# 12_Supply.net
KiCad netlist of a schematic drawn in Altium Designer
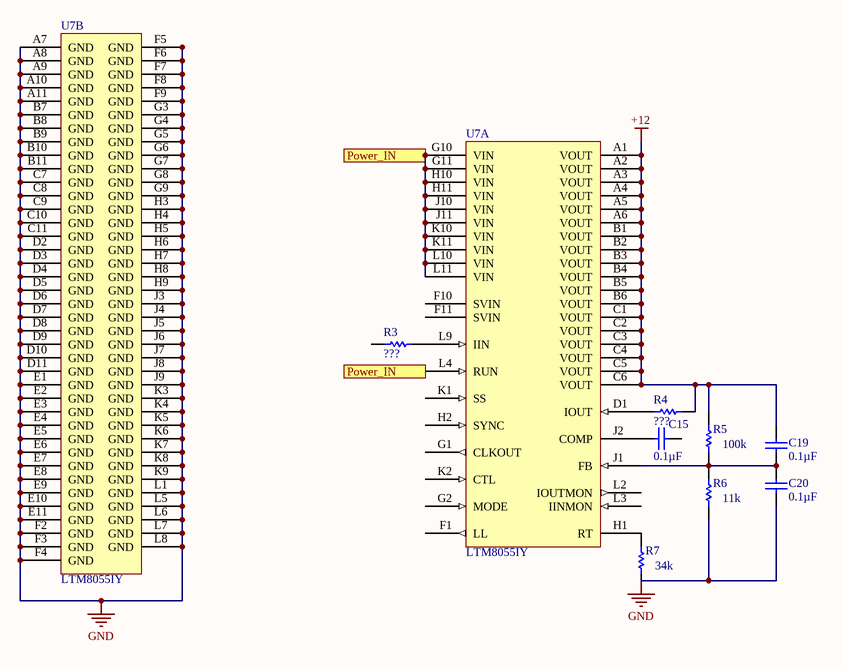
[diagram p0: 12_Supply.SchDoc]

(export (version "E")
  (design (tool "Eeschema 10.0.6"))
  (components
    (comp (ref "C15")
      (value "CAP CER 0.1UF 16V X7R 0805")
      (footprint "CAPC0805(2012)145_N")
      (fields
        (field (name "TOLERANCE") "±10%")
        (field (name "MANUFACTURER") "Murata Electronics North America")
        (field (name "MANUFACTURER PART NUMBER") "GRM219R71C104KA01D")
        (field (name "CAPACITANCE") "0.1µF")
      )
      (libsource (lib "Altium Content Vault") (part "CMP-1036-04795-1"))
    )
    (comp (ref "C19")
      (value "CAP CER 0.1UF 16V X7R 0805")
      (footprint "CAPC0805(2012)145_N")
      (fields
        (field (name "TOLERANCE") "±10%")
        (field (name "MANUFACTURER") "Murata Electronics North America")
        (field (name "MANUFACTURER PART NUMBER") "GRM219R71C104KA01D")
        (field (name "CAPACITANCE") "0.1µF")
      )
      (libsource (lib "Altium Content Vault") (part "CMP-1036-04795-1"))
    )
    (comp (ref "C20")
      (value "CAP CER 0.1UF 16V X7R 0805")
      (footprint "CAPC0805(2012)145_N")
      (fields
        (field (name "TOLERANCE") "±10%")
        (field (name "MANUFACTURER") "Murata Electronics North America")
        (field (name "MANUFACTURER PART NUMBER") "GRM219R71C104KA01D")
        (field (name "CAPACITANCE") "0.1µF")
      )
      (libsource (lib "Altium Content Vault") (part "CMP-1036-04795-1"))
    )
    (comp (ref "R3")
      (value "???")
      (footprint "RESC0402(1005)_L")
      (fields (field (name "TOLERANCE") "±1%"))
      (libsource (lib "Altium Content Vault") (part "CMP-1011-00927-1"))
    )
    (comp (ref "R4")
      (value "???")
      (footprint "RESC0402(1005)_L")
      (fields (field (name "TOLERANCE") "±1%"))
      (libsource (lib "Altium Content Vault") (part "CMP-1011-00927-1"))
    )
    (comp (ref "R5")
      (value "100k")
      (footprint "RESC0402(1005)_L")
      (fields (field (name "TOLERANCE") "±1%"))
      (libsource (lib "Altium Content Vault") (part "CMP-1011-00927-1"))
    )
    (comp (ref "R6")
      (value "11k")
      (footprint "RESC0402(1005)_L")
      (fields (field (name "TOLERANCE") "±1%"))
      (libsource (lib "Altium Content Vault") (part "CMP-1011-00927-1"))
    )
    (comp (ref "R7")
      (value "34k")
      (footprint "RESC0402(1005)_L")
      (fields (field (name "TOLERANCE") "±1%"))
      (libsource (lib "Altium Content Vault") (part "CMP-1011-00927-1"))
    )
    (comp (ref "U7")
      (value "LTM8055IY")
      (footprint "LT-BGA-121-15000X15000X4920")
      (description "Buck-Boost uModule Regulator, 8.5 A, 5 to 36 V, -40 to 125 degC, 121-Ball BGA, RoHS, Tray")
      (fields (field (name "MANUFACTURER") "LinearTechnology"))
      (libsource (lib "Altium Content Vault") (part "LT-LTM8055-BGA-121"))
    )
  )
  (nets
    (net (code "1") (name "+12") (class "Default")
      (node (ref "C19") (pin "2") (pinfunction "2_2") (pintype "passive"))
      (node (ref "R4") (pin "1") (pinfunction "1_1") (pintype "passive"))
      (node (ref "R5") (pin "2") (pinfunction "2_2") (pintype "passive"))
      (node (ref "U7") (pin "A1") (pinfunction "VOUT_A1") (pintype "power_in"))
      (node (ref "U7") (pin "A2") (pinfunction "VOUT_A2") (pintype "power_in"))
      (node (ref "U7") (pin "A3") (pinfunction "VOUT_A3") (pintype "power_in"))
      (node (ref "U7") (pin "A4") (pinfunction "VOUT_A4") (pintype "power_in"))
      (node (ref "U7") (pin "A5") (pinfunction "VOUT_A5") (pintype "power_in"))
      (node (ref "U7") (pin "A6") (pinfunction "VOUT_A6") (pintype "power_in"))
      (node (ref "U7") (pin "B1") (pinfunction "VOUT_B1") (pintype "power_in"))
      (node (ref "U7") (pin "B2") (pinfunction "VOUT_B2") (pintype "power_in"))
      (node (ref "U7") (pin "B3") (pinfunction "VOUT_B3") (pintype "power_in"))
      (node (ref "U7") (pin "B4") (pinfunction "VOUT_B4") (pintype "power_in"))
      (node (ref "U7") (pin "B5") (pinfunction "VOUT_B5") (pintype "power_in"))
      (node (ref "U7") (pin "B6") (pinfunction "VOUT_B6") (pintype "power_in"))
      (node (ref "U7") (pin "C1") (pinfunction "VOUT_C1") (pintype "power_in"))
      (node (ref "U7") (pin "C2") (pinfunction "VOUT_C2") (pintype "power_in"))
      (node (ref "U7") (pin "C3") (pinfunction "VOUT_C3") (pintype "power_in"))
      (node (ref "U7") (pin "C4") (pinfunction "VOUT_C4") (pintype "power_in"))
      (node (ref "U7") (pin "C5") (pinfunction "VOUT_C5") (pintype "power_in"))
      (node (ref "U7") (pin "C6") (pinfunction "VOUT_C6") (pintype "power_in"))
    )
    (net (code "2") (name "/Power_IN") (class "Default")
      (node (ref "U7") (pin "G10") (pinfunction "VIN_G10") (pintype "power_in"))
      (node (ref "U7") (pin "G11") (pinfunction "VIN_G11") (pintype "power_in"))
      (node (ref "U7") (pin "H10") (pinfunction "VIN_H10") (pintype "power_in"))
      (node (ref "U7") (pin "H11") (pinfunction "VIN_H11") (pintype "power_in"))
      (node (ref "U7") (pin "J10") (pinfunction "VIN_J10") (pintype "power_in"))
      (node (ref "U7") (pin "J11") (pinfunction "VIN_J11") (pintype "power_in"))
      (node (ref "U7") (pin "K10") (pinfunction "VIN_K10") (pintype "power_in"))
      (node (ref "U7") (pin "K11") (pinfunction "VIN_K11") (pintype "power_in"))
      (node (ref "U7") (pin "L10") (pinfunction "VIN_L10") (pintype "power_in"))
      (node (ref "U7") (pin "L11") (pinfunction "VIN_L11") (pintype "power_in"))
      (node (ref "U7") (pin "L4") (pinfunction "RUN_L4") (pintype "input"))
    )
    (net (code "3") (name "GND") (class "Default")
      (node (ref "C20") (pin "1") (pinfunction "1_1") (pintype "passive"))
      (node (ref "R6") (pin "1") (pinfunction "1_1") (pintype "passive"))
      (node (ref "U7") (pin "A10") (pinfunction "GND_A10") (pintype "power_in"))
      (node (ref "U7") (pin "A11") (pinfunction "GND_A11") (pintype "power_in"))
      (node (ref "U7") (pin "A7") (pinfunction "GND_A7") (pintype "power_in"))
      (node (ref "U7") (pin "A8") (pinfunction "GND_A8") (pintype "power_in"))
      (node (ref "U7") (pin "A9") (pinfunction "GND_A9") (pintype "power_in"))
      (node (ref "U7") (pin "B10") (pinfunction "GND_B10") (pintype "power_in"))
      (node (ref "U7") (pin "B11") (pinfunction "GND_B11") (pintype "power_in"))
      (node (ref "U7") (pin "B7") (pinfunction "GND_B7") (pintype "power_in"))
      (node (ref "U7") (pin "B8") (pinfunction "GND_B8") (pintype "power_in"))
      (node (ref "U7") (pin "B9") (pinfunction "GND_B9") (pintype "power_in"))
      (node (ref "U7") (pin "C10") (pinfunction "GND_C10") (pintype "power_in"))
      (node (ref "U7") (pin "C11") (pinfunction "GND_C11") (pintype "power_in"))
      (node (ref "U7") (pin "C7") (pinfunction "GND_C7") (pintype "power_in"))
      (node (ref "U7") (pin "C8") (pinfunction "GND_C8") (pintype "power_in"))
      (node (ref "U7") (pin "C9") (pinfunction "GND_C9") (pintype "power_in"))
      (node (ref "U7") (pin "D10") (pinfunction "GND_D10") (pintype "power_in"))
      (node (ref "U7") (pin "D11") (pinfunction "GND_D11") (pintype "power_in"))
      (node (ref "U7") (pin "D2") (pinfunction "GND_D2") (pintype "power_in"))
      (node (ref "U7") (pin "D3") (pinfunction "GND_D3") (pintype "power_in"))
      (node (ref "U7") (pin "D4") (pinfunction "GND_D4") (pintype "power_in"))
      (node (ref "U7") (pin "D5") (pinfunction "GND_D5") (pintype "power_in"))
      (node (ref "U7") (pin "D6") (pinfunction "GND_D6") (pintype "power_in"))
      (node (ref "U7") (pin "D7") (pinfunction "GND_D7") (pintype "power_in"))
      (node (ref "U7") (pin "D8") (pinfunction "GND_D8") (pintype "power_in"))
      (node (ref "U7") (pin "D9") (pinfunction "GND_D9") (pintype "power_in"))
      (node (ref "U7") (pin "E1") (pinfunction "GND_E1") (pintype "power_in"))
      (node (ref "U7") (pin "E10") (pinfunction "GND_E10") (pintype "power_in"))
      (node (ref "U7") (pin "E11") (pinfunction "GND_E11") (pintype "power_in"))
      (node (ref "U7") (pin "E2") (pinfunction "GND_E2") (pintype "power_in"))
      (node (ref "U7") (pin "E3") (pinfunction "GND_E3") (pintype "power_in"))
      (node (ref "U7") (pin "E4") (pinfunction "GND_E4") (pintype "power_in"))
      (node (ref "U7") (pin "E5") (pinfunction "GND_E5") (pintype "power_in"))
      (node (ref "U7") (pin "E6") (pinfunction "GND_E6") (pintype "power_in"))
      (node (ref "U7") (pin "E7") (pinfunction "GND_E7") (pintype "power_in"))
      (node (ref "U7") (pin "E8") (pinfunction "GND_E8") (pintype "power_in"))
      (node (ref "U7") (pin "E9") (pinfunction "GND_E9") (pintype "power_in"))
      (node (ref "U7") (pin "F2") (pinfunction "GND_F2") (pintype "power_in"))
      (node (ref "U7") (pin "F3") (pinfunction "GND_F3") (pintype "power_in"))
      (node (ref "U7") (pin "F4") (pinfunction "GND_F4") (pintype "power_in"))
      (node (ref "U7") (pin "F5") (pinfunction "GND_F5") (pintype "power_in"))
      (node (ref "U7") (pin "F6") (pinfunction "GND_F6") (pintype "power_in"))
      (node (ref "U7") (pin "F7") (pinfunction "GND_F7") (pintype "power_in"))
      (node (ref "U7") (pin "F8") (pinfunction "GND_F8") (pintype "power_in"))
      (node (ref "U7") (pin "F9") (pinfunction "GND_F9") (pintype "power_in"))
      (node (ref "U7") (pin "G3") (pinfunction "GND_G3") (pintype "power_in"))
      (node (ref "U7") (pin "G4") (pinfunction "GND_G4") (pintype "power_in"))
      (node (ref "U7") (pin "G5") (pinfunction "GND_G5") (pintype "power_in"))
      (node (ref "U7") (pin "G6") (pinfunction "GND_G6") (pintype "power_in"))
      (node (ref "U7") (pin "G7") (pinfunction "GND_G7") (pintype "power_in"))
      (node (ref "U7") (pin "G8") (pinfunction "GND_G8") (pintype "power_in"))
      (node (ref "U7") (pin "G9") (pinfunction "GND_G9") (pintype "power_in"))
      (node (ref "U7") (pin "H3") (pinfunction "GND_H3") (pintype "power_in"))
      (node (ref "U7") (pin "H4") (pinfunction "GND_H4") (pintype "power_in"))
      (node (ref "U7") (pin "H5") (pinfunction "GND_H5") (pintype "power_in"))
      (node (ref "U7") (pin "H6") (pinfunction "GND_H6") (pintype "power_in"))
      (node (ref "U7") (pin "H7") (pinfunction "GND_H7") (pintype "power_in"))
      (node (ref "U7") (pin "H8") (pinfunction "GND_H8") (pintype "power_in"))
      (node (ref "U7") (pin "H9") (pinfunction "GND_H9") (pintype "power_in"))
      (node (ref "U7") (pin "J3") (pinfunction "GND_J3") (pintype "power_in"))
      (node (ref "U7") (pin "J4") (pinfunction "GND_J4") (pintype "power_in"))
      (node (ref "U7") (pin "J5") (pinfunction "GND_J5") (pintype "power_in"))
      (node (ref "U7") (pin "J6") (pinfunction "GND_J6") (pintype "power_in"))
      (node (ref "U7") (pin "J7") (pinfunction "GND_J7") (pintype "power_in"))
      (node (ref "U7") (pin "J8") (pinfunction "GND_J8") (pintype "power_in"))
      (node (ref "U7") (pin "J9") (pinfunction "GND_J9") (pintype "power_in"))
      (node (ref "U7") (pin "K3") (pinfunction "GND_K3") (pintype "power_in"))
      (node (ref "U7") (pin "K4") (pinfunction "GND_K4") (pintype "power_in"))
      (node (ref "U7") (pin "K5") (pinfunction "GND_K5") (pintype "power_in"))
      (node (ref "U7") (pin "K6") (pinfunction "GND_K6") (pintype "power_in"))
      (node (ref "U7") (pin "K7") (pinfunction "GND_K7") (pintype "power_in"))
      (node (ref "U7") (pin "K8") (pinfunction "GND_K8") (pintype "power_in"))
      (node (ref "U7") (pin "K9") (pinfunction "GND_K9") (pintype "power_in"))
      (node (ref "U7") (pin "L1") (pinfunction "GND_L1") (pintype "power_in"))
      (node (ref "U7") (pin "L5") (pinfunction "GND_L5") (pintype "power_in"))
      (node (ref "U7") (pin "L6") (pinfunction "GND_L6") (pintype "power_in"))
      (node (ref "U7") (pin "L7") (pinfunction "GND_L7") (pintype "power_in"))
      (node (ref "U7") (pin "L8") (pinfunction "GND_L8") (pintype "power_in"))
    )
    (net (code "4") (name "Net-(U7A-COMP)") (class "Default")
      (node (ref "C15") (pin "1") (pinfunction "1_1") (pintype "passive"))
      (node (ref "U7") (pin "J2") (pinfunction "COMP_J2") (pintype "passive"))
    )
    (net (code "5") (name "Net-(U7A-FB)") (class "Default")
      (node (ref "C19") (pin "1") (pinfunction "1_1") (pintype "passive"))
      (node (ref "C20") (pin "2") (pinfunction "2_2") (pintype "passive"))
      (node (ref "R5") (pin "1") (pinfunction "1_1") (pintype "passive"))
      (node (ref "R6") (pin "2") (pinfunction "2_2") (pintype "passive"))
      (node (ref "U7") (pin "J1") (pinfunction "FB_J1") (pintype "input"))
    )
    (net (code "6") (name "Net-(U7A-IIN)") (class "Default")
      (node (ref "R3") (pin "1") (pinfunction "1_1") (pintype "passive"))
      (node (ref "U7") (pin "L9") (pinfunction "IIN_L9") (pintype "input"))
    )
    (net (code "7") (name "Net-(U7A-IOUT)") (class "Default")
      (node (ref "R4") (pin "2") (pinfunction "2_2") (pintype "passive"))
      (node (ref "U7") (pin "D1") (pinfunction "IOUT_D1") (pintype "input"))
    )
    (net (code "8") (name "Net-(U7A-RT)") (class "Default")
      (node (ref "R7") (pin "2") (pinfunction "2_2") (pintype "passive"))
      (node (ref "U7") (pin "H1") (pinfunction "RT_H1") (pintype "passive"))
    )
    (net (code "9") (name "unconnected-(C15-Pad2)") (class "Default")
      (node (ref "C15") (pin "2") (pinfunction "2_2") (pintype "passive"))
    )
    (net (code "10") (name "unconnected-(R3-Pad2)") (class "Default")
      (node (ref "R3") (pin "2") (pinfunction "2_2") (pintype "passive"))
    )
    (net (code "11") (name "unconnected-(R7-Pad1)") (class "Default")
      (node (ref "R7") (pin "1") (pinfunction "1_1") (pintype "passive"))
    )
    (net (code "12") (name "unconnected-(U7A-CLKOUT-PadG1)") (class "Default")
      (node (ref "U7") (pin "G1") (pinfunction "CLKOUT_G1") (pintype "output"))
    )
    (net (code "13") (name "unconnected-(U7A-CTL-PadK2)") (class "Default")
      (node (ref "U7") (pin "K2") (pinfunction "CTL_K2") (pintype "input"))
    )
    (net (code "14") (name "unconnected-(U7A-IINMON-PadL3)") (class "Default")
      (node (ref "U7") (pin "L3") (pinfunction "IINMON_L3") (pintype "input"))
    )
    (net (code "15") (name "unconnected-(U7A-IOUTMON-PadL2)") (class "Default")
      (node (ref "U7") (pin "L2") (pinfunction "IOUTMON_L2") (pintype "output"))
    )
    (net (code "16") (name "unconnected-(U7A-LL-PadF1)") (class "Default")
      (node (ref "U7") (pin "F1") (pinfunction "LL_F1") (pintype "output"))
    )
    (net (code "17") (name "unconnected-(U7A-MODE-PadG2)") (class "Default")
      (node (ref "U7") (pin "G2") (pinfunction "MODE_G2") (pintype "input"))
    )
    (net (code "18") (name "unconnected-(U7A-SS-PadK1)") (class "Default")
      (node (ref "U7") (pin "K1") (pinfunction "SS_K1") (pintype "input"))
    )
    (net (code "19") (name "unconnected-(U7A-SVIN-PadF10)") (class "Default")
      (node (ref "U7") (pin "F10") (pinfunction "SVIN_F10") (pintype "power_in"))
    )
    (net (code "20") (name "unconnected-(U7A-SVIN-PadF11)") (class "Default")
      (node (ref "U7") (pin "F11") (pinfunction "SVIN_F11") (pintype "power_in"))
    )
    (net (code "21") (name "unconnected-(U7A-SYNC-PadH2)") (class "Default")
      (node (ref "U7") (pin "H2") (pinfunction "SYNC_H2") (pintype "input"))
    )
  )
)
